# Sensors.net
KiCad netlist of a schematic drawn in Altium Designer
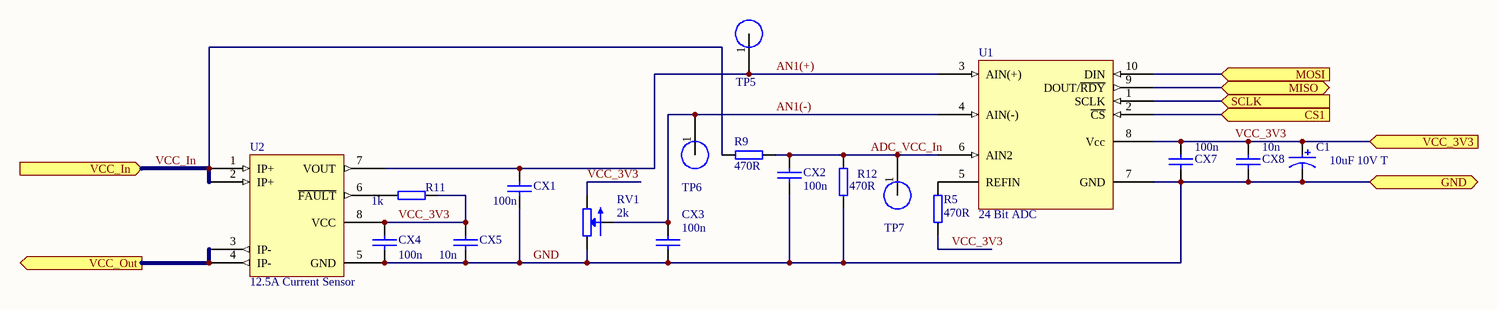
[diagram p0: Sensors.SchDoc]

(export (version "E")
  (design (tool "Eeschema 10.0.6"))
  (components
    (comp (ref "C1")
      (value "10uF 10V T")
      (footprint "SMD-TANT-A")
      (libsource (lib "DEVICE") (part "CAPACITOR POL-S"))
    )
    (comp (ref "CX1") (value "100n") (footprint "0603") (libsource (lib "*") (part "CAP")))
    (comp (ref "CX2") (value "100n") (footprint "0603") (libsource (lib "DEVICE") (part "CAP")))
    (comp (ref "CX3") (value "100n") (footprint "0603") (libsource (lib "*") (part "CAP")))
    (comp (ref "CX4") (value "100n") (footprint "0603") (libsource (lib "*") (part "CAP")))
    (comp (ref "CX5") (value "10n") (footprint "0603") (libsource (lib "*") (part "CAP")))
    (comp (ref "CX7") (value "100n") (footprint "0603") (libsource (lib "*") (part "CAP")))
    (comp (ref "CX8") (value "10n") (footprint "0603") (libsource (lib "*") (part "CAP")))
    (comp (ref "R5") (value "470R") (footprint "0603") (libsource (lib "DEVICE") (part "RES8")))
    (comp (ref "R9") (value "470R") (footprint "0603") (libsource (lib "DEVICE") (part "RES8")))
    (comp (ref "R11") (value "1k") (footprint "0603") (libsource (lib "DEVICE") (part "RES8")))
    (comp (ref "R12") (value "470R") (footprint "0603") (libsource (lib "DEVICE") (part "RES8")))
    (comp (ref "RV1") (value "2k") (footprint "VR3362P") (libsource (lib "DEVICE") (part "RES6")))
    (comp (ref "TP5")
      (value "TestPad")
      (footprint "TestPad")
      (description "Test Pad")
      (libsource (lib "Hardware") (part "TestPad"))
    )
    (comp (ref "TP6")
      (value "TestPad")
      (footprint "TestPad")
      (description "Test Pad")
      (libsource (lib "Hardware") (part "TestPad"))
    )
    (comp (ref "TP7")
      (value "TestPad")
      (footprint "TestPad")
      (description "Test Pad")
      (libsource (lib "Hardware") (part "TestPad"))
    )
    (comp (ref "U1")
      (value "24 Bit ADC")
      (footprint "MSOP-UN10_L")
      (description "AD7787BRMZ IC, 24BIT ADC, SMD, 7787, MSOP10")
      (libsource (lib "AnDev") (part "AD7787BRMZ 24Bit ADC"))
    )
    (comp (ref "U2")
      (value "12.5A Current Sensor")
      (footprint "SO-8")
      (description "ACS711")
      (libsource (lib "AllegroMicroSystems") (part "ACS711_12.5A_Current"))
    )
  )
  (nets
    (net (code "1") (name "/ADC_VCC_In") (class "Default")
      (node (ref "CX2") (pin "1") (pintype "passive"))
      (node (ref "R12") (pin "2") (pintype "passive"))
      (node (ref "R9") (pin "1") (pintype "passive"))
      (node (ref "TP7") (pin "1") (pintype "passive"))
      (node (ref "U1") (pin "6") (pinfunction "AIN2_6") (pintype "input"))
    )
    (net (code "2") (name "/AN1(+)") (class "Default")
      (node (ref "CX1") (pin "2") (pintype "passive"))
      (node (ref "TP5") (pin "1") (pintype "passive"))
      (node (ref "U1") (pin "3") (pinfunction "AIN(+)_3") (pintype "input"))
      (node (ref "U2") (pin "7") (pinfunction "VOUT_7") (pintype "output"))
    )
    (net (code "3") (name "/AN1(-)") (class "Default")
      (node (ref "CX3") (pin "2") (pintype "passive"))
      (node (ref "RV1") (pin "W") (pinfunction "W_W") (pintype "passive"))
      (node (ref "TP6") (pin "1") (pintype "passive"))
      (node (ref "U1") (pin "4") (pinfunction "AIN(-)_4") (pintype "input"))
    )
    (net (code "4") (name "/CS1") (class "Default")
      (node (ref "U1") (pin "2") (pinfunction "~{CS}_2") (pintype "input"))
    )
    (net (code "5") (name "/GND") (class "Default")
      (node (ref "C1") (pin "2") (pinfunction "2_2") (pintype "passive"))
      (node (ref "CX1") (pin "1") (pintype "passive"))
      (node (ref "CX2") (pin "2") (pintype "passive"))
      (node (ref "CX3") (pin "1") (pintype "passive"))
      (node (ref "CX4") (pin "1") (pintype "passive"))
      (node (ref "CX5") (pin "1") (pintype "passive"))
      (node (ref "CX7") (pin "1") (pintype "passive"))
      (node (ref "CX8") (pin "1") (pintype "passive"))
      (node (ref "R12") (pin "1") (pintype "passive"))
      (node (ref "RV1") (pin "CCW") (pinfunction "CCW_CCW") (pintype "passive"))
      (node (ref "U1") (pin "7") (pinfunction "GND_7") (pintype "power_in"))
      (node (ref "U2") (pin "5") (pinfunction "GND_5") (pintype "power_in"))
    )
    (net (code "6") (name "/MISO") (class "Default")
      (node (ref "U1") (pin "9") (pinfunction "DOUT/~{RDY}_9") (pintype "output"))
    )
    (net (code "7") (name "/MOSI") (class "Default")
      (node (ref "U1") (pin "10") (pinfunction "DIN_10") (pintype "input"))
    )
    (net (code "8") (name "/SCLK") (class "Default")
      (node (ref "U1") (pin "1") (pinfunction "SCLK_1") (pintype "input"))
    )
    (net (code "9") (name "/VCC_3V3") (class "Default")
      (node (ref "C1") (pin "1") (pinfunction "1_1") (pintype "passive"))
      (node (ref "CX4") (pin "2") (pintype "passive"))
      (node (ref "CX5") (pin "2") (pintype "passive"))
      (node (ref "CX7") (pin "2") (pintype "passive"))
      (node (ref "CX8") (pin "2") (pintype "passive"))
      (node (ref "R11") (pin "1") (pintype "passive"))
      (node (ref "R5") (pin "2") (pintype "passive"))
      (node (ref "RV1") (pin "CW") (pinfunction "CW_CW") (pintype "passive"))
      (node (ref "U1") (pin "8") (pinfunction "Vcc_8") (pintype "power_in"))
      (node (ref "U2") (pin "8") (pinfunction "VCC_8") (pintype "power_in"))
    )
    (net (code "10") (name "/VCC_In") (class "Default")
      (node (ref "R9") (pin "2") (pintype "passive"))
      (node (ref "U2") (pin "1") (pinfunction "IP+_1") (pintype "input"))
      (node (ref "U2") (pin "2") (pinfunction "IP+_2") (pintype "input"))
    )
    (net (code "11") (name "/VCC_Out") (class "Default")
      (node (ref "U2") (pin "3") (pinfunction "IP-_3") (pintype "output"))
      (node (ref "U2") (pin "4") (pinfunction "IP-_4") (pintype "output"))
    )
    (net (code "12") (name "Net-(U1-REFIN)") (class "Default")
      (node (ref "R5") (pin "1") (pintype "passive"))
      (node (ref "U1") (pin "5") (pinfunction "REFIN_5") (pintype "tri_state"))
    )
    (net (code "13") (name "Net-(U2-~{FAULT})") (class "Default")
      (node (ref "R11") (pin "2") (pintype "passive"))
      (node (ref "U2") (pin "6") (pinfunction "~{FAULT}_6") (pintype "output"))
    )
  )
)
